# 15-StimChannelSelection.net
KiCad netlist of a schematic drawn in Altium Designer
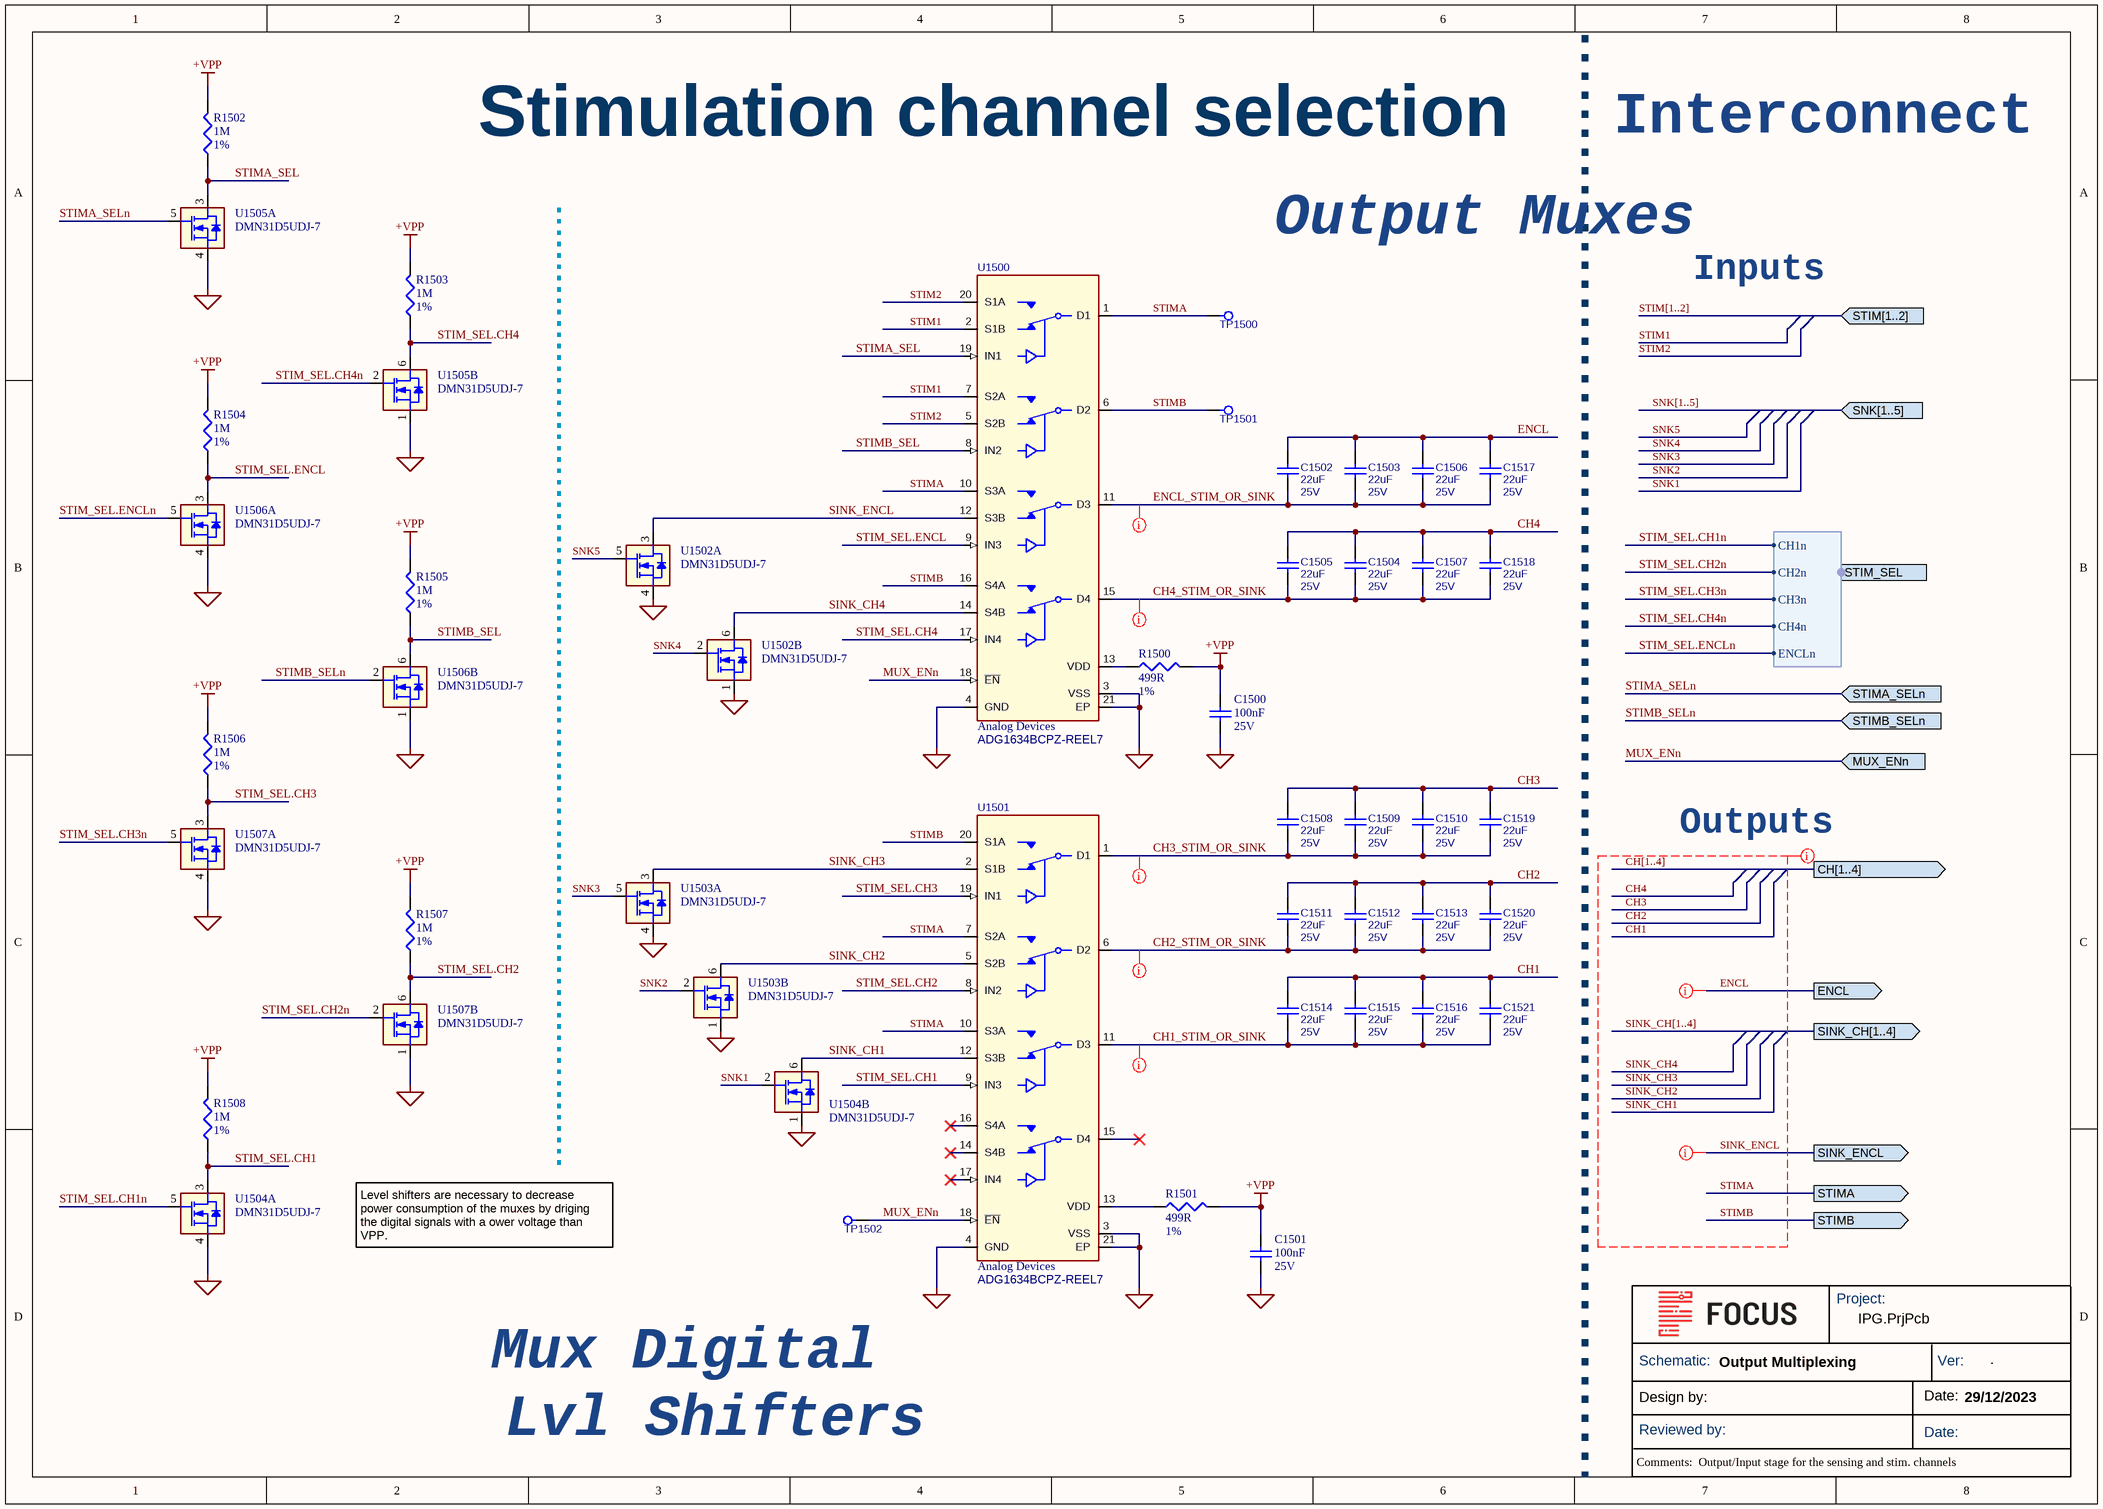
[diagram p0: 15-StimChannelSelection.SchDoc]

(export (version "E")
  (design (tool "Eeschema 10.0.6"))
  (components
    (comp (ref "C1500")
      (value "100nF")
      (footprint "C0201_C")
      (fields
        (field (name "MANUFACTURER") "Murata")
        (field (name "MANUFACTURER PART NUMBER") "GRM033R61E104KE14J")
        (field (name "RATED DC VOLTAGE (URDC)") "25V")
      )
      (libsource (lib "MP-LIBRARY") (part "GRM033R61E104KE14J"))
    )
    (comp (ref "C1501")
      (value "100nF")
      (footprint "C0201_C")
      (fields
        (field (name "MANUFACTURER") "Murata")
        (field (name "MANUFACTURER PART NUMBER") "GRM033R61E104KE14J")
        (field (name "RATED DC VOLTAGE (URDC)") "25V")
      )
      (libsource (lib "MP-LIBRARY") (part "GRM033R61E104KE14J"))
    )
    (comp (ref "C1502")
      (value "22uF")
      (footprint "C0603")
      (description "Capacitor, 22uF, X5S, 25V, 20%, 0603")
      (fields
        (field (name "MANUFACTURER") "Murata")
        (field (name "MANUFACTURER PART NUMBER") "GRM188C61E226ME01J")
        (field (name "RATING") "25V")
      )
      (libsource (lib "MP-LIBRARY") (part "GRM188C61E226ME01J"))
    )
    (comp (ref "C1503")
      (value "22uF")
      (footprint "C0603")
      (description "Capacitor, 22uF, X5S, 25V, 20%, 0603")
      (fields
        (field (name "MANUFACTURER") "Murata")
        (field (name "MANUFACTURER PART NUMBER") "GRM188C61E226ME01J")
        (field (name "RATING") "25V")
      )
      (libsource (lib "MP-LIBRARY") (part "GRM188C61E226ME01J"))
    )
    (comp (ref "C1504")
      (value "22uF")
      (footprint "C0603")
      (description "Capacitor, 22uF, X5S, 25V, 20%, 0603")
      (fields
        (field (name "MANUFACTURER") "Murata")
        (field (name "MANUFACTURER PART NUMBER") "GRM188C61E226ME01J")
        (field (name "RATING") "25V")
      )
      (libsource (lib "MP-LIBRARY") (part "GRM188C61E226ME01J"))
    )
    (comp (ref "C1505")
      (value "22uF")
      (footprint "C0603")
      (description "Capacitor, 22uF, X5S, 25V, 20%, 0603")
      (fields
        (field (name "MANUFACTURER") "Murata")
        (field (name "MANUFACTURER PART NUMBER") "GRM188C61E226ME01J")
        (field (name "RATING") "25V")
      )
      (libsource (lib "MP-LIBRARY") (part "GRM188C61E226ME01J"))
    )
    (comp (ref "C1506")
      (value "22uF")
      (footprint "C0603")
      (description "Capacitor, 22uF, X5S, 25V, 20%, 0603")
      (fields
        (field (name "MANUFACTURER") "Murata")
        (field (name "MANUFACTURER PART NUMBER") "GRM188C61E226ME01J")
        (field (name "RATING") "25V")
      )
      (libsource (lib "MP-LIBRARY") (part "GRM188C61E226ME01J"))
    )
    (comp (ref "C1507")
      (value "22uF")
      (footprint "C0603")
      (description "Capacitor, 22uF, X5S, 25V, 20%, 0603")
      (fields
        (field (name "MANUFACTURER") "Murata")
        (field (name "MANUFACTURER PART NUMBER") "GRM188C61E226ME01J")
        (field (name "RATING") "25V")
      )
      (libsource (lib "MP-LIBRARY") (part "GRM188C61E226ME01J"))
    )
    (comp (ref "C1508")
      (value "22uF")
      (footprint "C0603")
      (description "Capacitor, 22uF, X5S, 25V, 20%, 0603")
      (fields
        (field (name "MANUFACTURER") "Murata")
        (field (name "MANUFACTURER PART NUMBER") "GRM188C61E226ME01J")
        (field (name "RATING") "25V")
      )
      (libsource (lib "MP-LIBRARY") (part "GRM188C61E226ME01J"))
    )
    (comp (ref "C1509")
      (value "22uF")
      (footprint "C0603")
      (description "Capacitor, 22uF, X5S, 25V, 20%, 0603")
      (fields
        (field (name "MANUFACTURER") "Murata")
        (field (name "MANUFACTURER PART NUMBER") "GRM188C61E226ME01J")
        (field (name "RATING") "25V")
      )
      (libsource (lib "MP-LIBRARY") (part "GRM188C61E226ME01J"))
    )
    (comp (ref "C1510")
      (value "22uF")
      (footprint "C0603")
      (description "Capacitor, 22uF, X5S, 25V, 20%, 0603")
      (fields
        (field (name "MANUFACTURER") "Murata")
        (field (name "MANUFACTURER PART NUMBER") "GRM188C61E226ME01J")
        (field (name "RATING") "25V")
      )
      (libsource (lib "MP-LIBRARY") (part "GRM188C61E226ME01J"))
    )
    (comp (ref "C1511")
      (value "22uF")
      (footprint "C0603")
      (description "Capacitor, 22uF, X5S, 25V, 20%, 0603")
      (fields
        (field (name "MANUFACTURER") "Murata")
        (field (name "MANUFACTURER PART NUMBER") "GRM188C61E226ME01J")
        (field (name "RATING") "25V")
      )
      (libsource (lib "MP-LIBRARY") (part "GRM188C61E226ME01J"))
    )
    (comp (ref "C1512")
      (value "22uF")
      (footprint "C0603")
      (description "Capacitor, 22uF, X5S, 25V, 20%, 0603")
      (fields
        (field (name "MANUFACTURER") "Murata")
        (field (name "MANUFACTURER PART NUMBER") "GRM188C61E226ME01J")
        (field (name "RATING") "25V")
      )
      (libsource (lib "MP-LIBRARY") (part "GRM188C61E226ME01J"))
    )
    (comp (ref "C1513")
      (value "22uF")
      (footprint "C0603")
      (description "Capacitor, 22uF, X5S, 25V, 20%, 0603")
      (fields
        (field (name "MANUFACTURER") "Murata")
        (field (name "MANUFACTURER PART NUMBER") "GRM188C61E226ME01J")
        (field (name "RATING") "25V")
      )
      (libsource (lib "MP-LIBRARY") (part "GRM188C61E226ME01J"))
    )
    (comp (ref "C1514")
      (value "22uF")
      (footprint "C0603")
      (description "Capacitor, 22uF, X5S, 25V, 20%, 0603")
      (fields
        (field (name "MANUFACTURER") "Murata")
        (field (name "MANUFACTURER PART NUMBER") "GRM188C61E226ME01J")
        (field (name "RATING") "25V")
      )
      (libsource (lib "MP-LIBRARY") (part "GRM188C61E226ME01J"))
    )
    (comp (ref "C1515")
      (value "22uF")
      (footprint "C0603")
      (description "Capacitor, 22uF, X5S, 25V, 20%, 0603")
      (fields
        (field (name "MANUFACTURER") "Murata")
        (field (name "MANUFACTURER PART NUMBER") "GRM188C61E226ME01J")
        (field (name "RATING") "25V")
      )
      (libsource (lib "MP-LIBRARY") (part "GRM188C61E226ME01J"))
    )
    (comp (ref "C1516")
      (value "22uF")
      (footprint "C0603")
      (description "Capacitor, 22uF, X5S, 25V, 20%, 0603")
      (fields
        (field (name "MANUFACTURER") "Murata")
        (field (name "MANUFACTURER PART NUMBER") "GRM188C61E226ME01J")
        (field (name "RATING") "25V")
      )
      (libsource (lib "MP-LIBRARY") (part "GRM188C61E226ME01J"))
    )
    (comp (ref "C1517")
      (value "22uF")
      (footprint "C0603")
      (description "Capacitor, 22uF, X5S, 25V, 20%, 0603")
      (fields
        (field (name "MANUFACTURER") "Murata")
        (field (name "MANUFACTURER PART NUMBER") "GRM188C61E226ME01J")
        (field (name "RATING") "25V")
      )
      (libsource (lib "MP-LIBRARY") (part "GRM188C61E226ME01J"))
    )
    (comp (ref "C1518")
      (value "22uF")
      (footprint "C0603")
      (description "Capacitor, 22uF, X5S, 25V, 20%, 0603")
      (fields
        (field (name "MANUFACTURER") "Murata")
        (field (name "MANUFACTURER PART NUMBER") "GRM188C61E226ME01J")
        (field (name "RATING") "25V")
      )
      (libsource (lib "MP-LIBRARY") (part "GRM188C61E226ME01J"))
    )
    (comp (ref "C1519")
      (value "22uF")
      (footprint "C0603")
      (description "Capacitor, 22uF, X5S, 25V, 20%, 0603")
      (fields
        (field (name "MANUFACTURER") "Murata")
        (field (name "MANUFACTURER PART NUMBER") "GRM188C61E226ME01J")
        (field (name "RATING") "25V")
      )
      (libsource (lib "MP-LIBRARY") (part "GRM188C61E226ME01J"))
    )
    (comp (ref "C1520")
      (value "22uF")
      (footprint "C0603")
      (description "Capacitor, 22uF, X5S, 25V, 20%, 0603")
      (fields
        (field (name "MANUFACTURER") "Murata")
        (field (name "MANUFACTURER PART NUMBER") "GRM188C61E226ME01J")
        (field (name "RATING") "25V")
      )
      (libsource (lib "MP-LIBRARY") (part "GRM188C61E226ME01J"))
    )
    (comp (ref "C1521")
      (value "22uF")
      (footprint "C0603")
      (description "Capacitor, 22uF, X5S, 25V, 20%, 0603")
      (fields
        (field (name "MANUFACTURER") "Murata")
        (field (name "MANUFACTURER PART NUMBER") "GRM188C61E226ME01J")
        (field (name "RATING") "25V")
      )
      (libsource (lib "MP-LIBRARY") (part "GRM188C61E226ME01J"))
    )
    (comp (ref "R1500")
      (value "499R")
      (footprint "RES0402_REDUCED")
      (fields
        (field (name "MANUFACTURER") "Vishay Dale")
        (field (name "MANUFACTURER PART NUMBER") "CRCW0402499RFKEDHP")
        (field (name "POWER") "200mW")
        (field (name "TOLERANCE") "1%")
      )
      (libsource (lib "MP-LIBRARY") (part "CRCW0402499RFKEDHP"))
    )
    (comp (ref "R1501")
      (value "499R")
      (footprint "RES0402_REDUCED")
      (fields
        (field (name "MANUFACTURER") "Vishay Dale")
        (field (name "MANUFACTURER PART NUMBER") "CRCW0402499RFKEDHP")
        (field (name "POWER") "200mW")
        (field (name "TOLERANCE") "1%")
      )
      (libsource (lib "MP-LIBRARY") (part "CRCW0402499RFKEDHP"))
    )
    (comp (ref "R1502")
      (value "1M")
      (footprint "R0201_C")
      (fields
        (field (name "MANUFACTURER") "Vishay")
        (field (name "MANUFACTURER PART NUMBER") "CRCW02011M00FNED")
        (field (name "TOLERANCE") "1%")
        (field (name "POWER") "50mW")
      )
      (libsource (lib "MP-LIBRARY") (part "CRCW02011M00FNED"))
    )
    (comp (ref "R1503")
      (value "1M")
      (footprint "R0201_C")
      (fields
        (field (name "MANUFACTURER") "Vishay")
        (field (name "MANUFACTURER PART NUMBER") "CRCW02011M00FNED")
        (field (name "TOLERANCE") "1%")
        (field (name "POWER") "50mW")
      )
      (libsource (lib "MP-LIBRARY") (part "CRCW02011M00FNED"))
    )
    (comp (ref "R1504")
      (value "1M")
      (footprint "R0201_C")
      (fields
        (field (name "MANUFACTURER") "Vishay")
        (field (name "MANUFACTURER PART NUMBER") "CRCW02011M00FNED")
        (field (name "TOLERANCE") "1%")
        (field (name "POWER") "50mW")
      )
      (libsource (lib "MP-LIBRARY") (part "CRCW02011M00FNED"))
    )
    (comp (ref "R1505")
      (value "1M")
      (footprint "R0201_C")
      (fields
        (field (name "MANUFACTURER") "Vishay")
        (field (name "MANUFACTURER PART NUMBER") "CRCW02011M00FNED")
        (field (name "TOLERANCE") "1%")
        (field (name "POWER") "50mW")
      )
      (libsource (lib "MP-LIBRARY") (part "CRCW02011M00FNED"))
    )
    (comp (ref "R1506")
      (value "1M")
      (footprint "R0201_C")
      (fields
        (field (name "MANUFACTURER") "Vishay")
        (field (name "MANUFACTURER PART NUMBER") "CRCW02011M00FNED")
        (field (name "TOLERANCE") "1%")
        (field (name "POWER") "50mW")
      )
      (libsource (lib "MP-LIBRARY") (part "CRCW02011M00FNED"))
    )
    (comp (ref "R1507")
      (value "1M")
      (footprint "R0201_C")
      (fields
        (field (name "MANUFACTURER") "Vishay")
        (field (name "MANUFACTURER PART NUMBER") "CRCW02011M00FNED")
        (field (name "TOLERANCE") "1%")
        (field (name "POWER") "50mW")
      )
      (libsource (lib "MP-LIBRARY") (part "CRCW02011M00FNED"))
    )
    (comp (ref "R1508")
      (value "1M")
      (footprint "R0201_C")
      (fields
        (field (name "MANUFACTURER") "Vishay")
        (field (name "MANUFACTURER PART NUMBER") "CRCW02011M00FNED")
        (field (name "TOLERANCE") "1%")
        (field (name "POWER") "50mW")
      )
      (libsource (lib "MP-LIBRARY") (part "CRCW02011M00FNED"))
    )
    (comp (ref "TP1500")
      (value "Test Point")
      (footprint "testpad_0.9mm")
      (description "Test pad, 0.90mm circular pad")
      (libsource (lib "MP-LIBRARY") (part "Test Point"))
    )
    (comp (ref "TP1501")
      (value "Test Point")
      (footprint "testpad_0.9mm")
      (description "Test pad, 0.90mm circular pad")
      (libsource (lib "MP-LIBRARY") (part "Test Point"))
    )
    (comp (ref "TP1502")
      (value "Test Point")
      (footprint "testpad_0.9mm")
      (description "Test pad, 0.90mm circular pad")
      (libsource (lib "MP-LIBRARY") (part "Test Point"))
    )
    (comp (ref "U1500")
      (value "ADG1634BCPZ-REEL7")
      (footprint "AD_CP-20-10")
      (description "IC SWITCH SPDTX4 4.5OHM 20LFCSP")
      (fields (field (name "MANUFACTURER") "Analog Devices"))
      (libsource (lib "MP-LIBRARY") (part "ADG1634BCPZ-REEL7"))
    )
    (comp (ref "U1501")
      (value "ADG1634BCPZ-REEL7")
      (footprint "AD_CP-20-10")
      (description "IC SWITCH SPDTX4 4.5OHM 20LFCSP")
      (fields (field (name "MANUFACTURER") "Analog Devices"))
      (libsource (lib "MP-LIBRARY") (part "ADG1634BCPZ-REEL7"))
    )
    (comp (ref "U1502")
      (value "DMN31D5UDJ-7")
      (footprint "DIODESINC_SOT-963-6")
      (description "MOSFET 2N-CH 30V 0.22A SOT963")
      (fields (field (name "MANUFACTURER") "Diodes inc."))
      (libsource (lib "MP-LIBRARY") (part "DMN31D5UDJ-7"))
    )
    (comp (ref "U1503")
      (value "DMN31D5UDJ-7")
      (footprint "DIODESINC_SOT-963-6")
      (description "MOSFET 2N-CH 30V 0.22A SOT963")
      (fields (field (name "MANUFACTURER") "Diodes inc."))
      (libsource (lib "MP-LIBRARY") (part "DMN31D5UDJ-7"))
    )
    (comp (ref "U1504")
      (value "DMN31D5UDJ-7")
      (footprint "DIODESINC_SOT-963-6")
      (description "MOSFET 2N-CH 30V 0.22A SOT963")
      (fields (field (name "MANUFACTURER") "Diodes inc."))
      (libsource (lib "MP-LIBRARY") (part "DMN31D5UDJ-7"))
    )
    (comp (ref "U1505")
      (value "DMN31D5UDJ-7")
      (footprint "DIODESINC_SOT-963-6")
      (description "MOSFET 2N-CH 30V 0.22A SOT963")
      (fields (field (name "MANUFACTURER") "Diodes inc."))
      (libsource (lib "MP-LIBRARY") (part "DMN31D5UDJ-7"))
    )
    (comp (ref "U1506")
      (value "DMN31D5UDJ-7")
      (footprint "DIODESINC_SOT-963-6")
      (description "MOSFET 2N-CH 30V 0.22A SOT963")
      (fields (field (name "MANUFACTURER") "Diodes inc."))
      (libsource (lib "MP-LIBRARY") (part "DMN31D5UDJ-7"))
    )
    (comp (ref "U1507")
      (value "DMN31D5UDJ-7")
      (footprint "DIODESINC_SOT-963-6")
      (description "MOSFET 2N-CH 30V 0.22A SOT963")
      (fields (field (name "MANUFACTURER") "Diodes inc."))
      (libsource (lib "MP-LIBRARY") (part "DMN31D5UDJ-7"))
    )
  )
  (nets
    (net (code "2") (name "+VPP") (class "Default")
      (node (ref "C1500") (pin "2") (pinfunction "2_2") (pintype "passive"))
      (node (ref "C1501") (pin "2") (pinfunction "2_2") (pintype "passive"))
      (node (ref "R1500") (pin "2") (pinfunction "2_2") (pintype "passive"))
      (node (ref "R1501") (pin "2") (pinfunction "2_2") (pintype "passive"))
      (node (ref "R1502") (pin "1") (pinfunction "1_1") (pintype "passive"))
      (node (ref "R1503") (pin "1") (pinfunction "1_1") (pintype "passive"))
      (node (ref "R1504") (pin "1") (pinfunction "1_1") (pintype "passive"))
      (node (ref "R1505") (pin "1") (pinfunction "1_1") (pintype "passive"))
      (node (ref "R1506") (pin "1") (pinfunction "1_1") (pintype "passive"))
      (node (ref "R1507") (pin "1") (pinfunction "1_1") (pintype "passive"))
      (node (ref "R1508") (pin "1") (pinfunction "1_1") (pintype "passive"))
    )
    (net (code "3") (name "/CH1") (class "Default")
      (node (ref "C1514") (pin "1") (pinfunction "1_1") (pintype "passive"))
      (node (ref "C1515") (pin "1") (pinfunction "1_1") (pintype "passive"))
      (node (ref "C1516") (pin "1") (pinfunction "1_1") (pintype "passive"))
      (node (ref "C1521") (pin "1") (pinfunction "1_1") (pintype "passive"))
    )
    (net (code "4") (name "/CH1_STIM_OR_SINK") (class "Default")
      (node (ref "C1514") (pin "2") (pinfunction "2_2") (pintype "passive"))
      (node (ref "C1515") (pin "2") (pinfunction "2_2") (pintype "passive"))
      (node (ref "C1516") (pin "2") (pinfunction "2_2") (pintype "passive"))
      (node (ref "C1521") (pin "2") (pinfunction "2_2") (pintype "passive"))
      (node (ref "U1501") (pin "11") (pinfunction "D3_11") (pintype "passive"))
    )
    (net (code "5") (name "/CH2") (class "Default")
      (node (ref "C1511") (pin "1") (pinfunction "1_1") (pintype "passive"))
      (node (ref "C1512") (pin "1") (pinfunction "1_1") (pintype "passive"))
      (node (ref "C1513") (pin "1") (pinfunction "1_1") (pintype "passive"))
      (node (ref "C1520") (pin "1") (pinfunction "1_1") (pintype "passive"))
    )
    (net (code "6") (name "/CH2_STIM_OR_SINK") (class "Default")
      (node (ref "C1511") (pin "2") (pinfunction "2_2") (pintype "passive"))
      (node (ref "C1512") (pin "2") (pinfunction "2_2") (pintype "passive"))
      (node (ref "C1513") (pin "2") (pinfunction "2_2") (pintype "passive"))
      (node (ref "C1520") (pin "2") (pinfunction "2_2") (pintype "passive"))
      (node (ref "U1501") (pin "6") (pinfunction "D2_6") (pintype "passive"))
    )
    (net (code "7") (name "/CH3") (class "Default")
      (node (ref "C1508") (pin "1") (pinfunction "1_1") (pintype "passive"))
      (node (ref "C1509") (pin "1") (pinfunction "1_1") (pintype "passive"))
      (node (ref "C1510") (pin "1") (pinfunction "1_1") (pintype "passive"))
      (node (ref "C1519") (pin "1") (pinfunction "1_1") (pintype "passive"))
    )
    (net (code "8") (name "/CH3_STIM_OR_SINK") (class "Default")
      (node (ref "C1508") (pin "2") (pinfunction "2_2") (pintype "passive"))
      (node (ref "C1509") (pin "2") (pinfunction "2_2") (pintype "passive"))
      (node (ref "C1510") (pin "2") (pinfunction "2_2") (pintype "passive"))
      (node (ref "C1519") (pin "2") (pinfunction "2_2") (pintype "passive"))
      (node (ref "U1501") (pin "1") (pinfunction "D1_1") (pintype "passive"))
    )
    (net (code "9") (name "/CH4") (class "Default")
      (node (ref "C1504") (pin "1") (pinfunction "1_1") (pintype "passive"))
      (node (ref "C1505") (pin "1") (pinfunction "1_1") (pintype "passive"))
      (node (ref "C1507") (pin "1") (pinfunction "1_1") (pintype "passive"))
      (node (ref "C1518") (pin "1") (pinfunction "1_1") (pintype "passive"))
    )
    (net (code "10") (name "/CH4_STIM_OR_SINK") (class "Default")
      (node (ref "C1504") (pin "2") (pinfunction "2_2") (pintype "passive"))
      (node (ref "C1505") (pin "2") (pinfunction "2_2") (pintype "passive"))
      (node (ref "C1507") (pin "2") (pinfunction "2_2") (pintype "passive"))
      (node (ref "C1518") (pin "2") (pinfunction "2_2") (pintype "passive"))
      (node (ref "U1500") (pin "15") (pinfunction "D4_15") (pintype "passive"))
    )
    (net (code "12") (name "/ENCL") (class "Default")
      (node (ref "C1502") (pin "2") (pinfunction "2_2") (pintype "passive"))
      (node (ref "C1503") (pin "2") (pinfunction "2_2") (pintype "passive"))
      (node (ref "C1506") (pin "2") (pinfunction "2_2") (pintype "passive"))
      (node (ref "C1517") (pin "1") (pinfunction "1_1") (pintype "passive"))
    )
    (net (code "13") (name "/ENCL_STIM_OR_SINK") (class "Default")
      (node (ref "C1502") (pin "1") (pinfunction "1_1") (pintype "passive"))
      (node (ref "C1503") (pin "1") (pinfunction "1_1") (pintype "passive"))
      (node (ref "C1506") (pin "1") (pinfunction "1_1") (pintype "passive"))
      (node (ref "C1517") (pin "2") (pinfunction "2_2") (pintype "passive"))
      (node (ref "U1500") (pin "11") (pinfunction "D3_11") (pintype "passive"))
    )
    (net (code "14") (name "/MUX_ENn") (class "Default")
      (node (ref "TP1502") (pin "1") (pinfunction "1_1") (pintype "passive"))
      (node (ref "U1500") (pin "18") (pinfunction "~{EN}_18") (pintype "input"))
      (node (ref "U1501") (pin "18") (pinfunction "~{EN}_18") (pintype "input"))
    )
    (net (code "15") (name "/SINK_CH1") (class "Default")
      (node (ref "U1501") (pin "12") (pinfunction "S3B_12") (pintype "passive"))
      (node (ref "U1504") (pin "6") (pinfunction "6_6") (pintype "passive"))
    )
    (net (code "16") (name "/SINK_CH2") (class "Default")
      (node (ref "U1501") (pin "5") (pinfunction "S2B_5") (pintype "passive"))
      (node (ref "U1503") (pin "6") (pinfunction "6_6") (pintype "passive"))
    )
    (net (code "17") (name "/SINK_CH3") (class "Default")
      (node (ref "U1501") (pin "2") (pinfunction "S1B_2") (pintype "passive"))
      (node (ref "U1503") (pin "3") (pinfunction "3_3") (pintype "passive"))
    )
    (net (code "18") (name "/SINK_CH4") (class "Default")
      (node (ref "U1500") (pin "14") (pinfunction "S4B_14") (pintype "passive"))
      (node (ref "U1502") (pin "6") (pinfunction "6_6") (pintype "passive"))
    )
    (net (code "20") (name "/SINK_ENCL") (class "Default")
      (node (ref "U1500") (pin "12") (pinfunction "S3B_12") (pintype "passive"))
      (node (ref "U1502") (pin "3") (pinfunction "3_3") (pintype "passive"))
    )
    (net (code "21") (name "/SNK1") (class "Default")
      (node (ref "U1504") (pin "2") (pinfunction "2_2") (pintype "passive"))
    )
    (net (code "22") (name "/SNK2") (class "Default")
      (node (ref "U1503") (pin "2") (pinfunction "2_2") (pintype "passive"))
    )
    (net (code "23") (name "/SNK3") (class "Default")
      (node (ref "U1503") (pin "5") (pinfunction "5_5") (pintype "passive"))
    )
    (net (code "24") (name "/SNK4") (class "Default")
      (node (ref "U1502") (pin "2") (pinfunction "2_2") (pintype "passive"))
    )
    (net (code "25") (name "/SNK5") (class "Default")
      (node (ref "U1502") (pin "5") (pinfunction "5_5") (pintype "passive"))
    )
    (net (code "27") (name "/STIM1") (class "Default")
      (node (ref "U1500") (pin "2") (pinfunction "S1B_2") (pintype "passive"))
      (node (ref "U1500") (pin "7") (pinfunction "S2A_7") (pintype "passive"))
    )
    (net (code "28") (name "/STIM2") (class "Default")
      (node (ref "U1500") (pin "20") (pinfunction "S1A_20") (pintype "passive"))
      (node (ref "U1500") (pin "5") (pinfunction "S2B_5") (pintype "passive"))
    )
    (net (code "29") (name "/STIMA") (class "Default")
      (node (ref "TP1500") (pin "1") (pinfunction "1_1") (pintype "passive"))
      (node (ref "U1500") (pin "1") (pinfunction "D1_1") (pintype "passive"))
      (node (ref "U1500") (pin "10") (pinfunction "S3A_10") (pintype "passive"))
      (node (ref "U1501") (pin "10") (pinfunction "S3A_10") (pintype "passive"))
      (node (ref "U1501") (pin "7") (pinfunction "S2A_7") (pintype "passive"))
    )
    (net (code "30") (name "/STIMA_SEL") (class "Default")
      (node (ref "R1502") (pin "2") (pinfunction "2_2") (pintype "passive"))
      (node (ref "U1500") (pin "19") (pinfunction "IN1_19") (pintype "input"))
      (node (ref "U1505") (pin "3") (pinfunction "3_3") (pintype "passive"))
    )
    (net (code "31") (name "/STIMA_SELn") (class "Default")
      (node (ref "U1505") (pin "5") (pinfunction "5_5") (pintype "passive"))
    )
    (net (code "32") (name "/STIMB") (class "Default")
      (node (ref "TP1501") (pin "1") (pinfunction "1_1") (pintype "passive"))
      (node (ref "U1500") (pin "16") (pinfunction "S4A_16") (pintype "passive"))
      (node (ref "U1500") (pin "6") (pinfunction "D2_6") (pintype "passive"))
      (node (ref "U1501") (pin "20") (pinfunction "S1A_20") (pintype "passive"))
    )
    (net (code "33") (name "/STIMB_SEL") (class "Default")
      (node (ref "R1505") (pin "2") (pinfunction "2_2") (pintype "passive"))
      (node (ref "U1500") (pin "8") (pinfunction "IN2_8") (pintype "input"))
      (node (ref "U1506") (pin "6") (pinfunction "6_6") (pintype "passive"))
    )
    (net (code "34") (name "/STIMB_SELn") (class "Default")
      (node (ref "U1506") (pin "2") (pinfunction "2_2") (pintype "passive"))
    )
    (net (code "36") (name "/STIM_SEL.CH1") (class "Default")
      (node (ref "R1508") (pin "2") (pinfunction "2_2") (pintype "passive"))
      (node (ref "U1501") (pin "9") (pinfunction "IN3_9") (pintype "input"))
      (node (ref "U1504") (pin "3") (pinfunction "3_3") (pintype "passive"))
    )
    (net (code "37") (name "/STIM_SEL.CH1n") (class "Default")
      (node (ref "U1504") (pin "5") (pinfunction "5_5") (pintype "passive"))
    )
    (net (code "38") (name "/STIM_SEL.CH2") (class "Default")
      (node (ref "R1507") (pin "2") (pinfunction "2_2") (pintype "passive"))
      (node (ref "U1501") (pin "8") (pinfunction "IN2_8") (pintype "input"))
      (node (ref "U1507") (pin "6") (pinfunction "6_6") (pintype "passive"))
    )
    (net (code "39") (name "/STIM_SEL.CH2n") (class "Default")
      (node (ref "U1507") (pin "2") (pinfunction "2_2") (pintype "passive"))
    )
    (net (code "40") (name "/STIM_SEL.CH3") (class "Default")
      (node (ref "R1506") (pin "2") (pinfunction "2_2") (pintype "passive"))
      (node (ref "U1501") (pin "19") (pinfunction "IN1_19") (pintype "input"))
      (node (ref "U1507") (pin "3") (pinfunction "3_3") (pintype "passive"))
    )
    (net (code "41") (name "/STIM_SEL.CH3n") (class "Default")
      (node (ref "U1507") (pin "5") (pinfunction "5_5") (pintype "passive"))
    )
    (net (code "42") (name "/STIM_SEL.CH4") (class "Default")
      (node (ref "R1503") (pin "2") (pinfunction "2_2") (pintype "passive"))
      (node (ref "U1500") (pin "17") (pinfunction "IN4_17") (pintype "input"))
      (node (ref "U1505") (pin "6") (pinfunction "6_6") (pintype "passive"))
    )
    (net (code "43") (name "/STIM_SEL.CH4n") (class "Default")
      (node (ref "U1505") (pin "2") (pinfunction "2_2") (pintype "passive"))
    )
    (net (code "44") (name "/STIM_SEL.ENCL") (class "Default")
      (node (ref "R1504") (pin "2") (pinfunction "2_2") (pintype "passive"))
      (node (ref "U1500") (pin "9") (pinfunction "IN3_9") (pintype "input"))
      (node (ref "U1506") (pin "3") (pinfunction "3_3") (pintype "passive"))
    )
    (net (code "45") (name "/STIM_SEL.ENCLn") (class "Default")
      (node (ref "U1506") (pin "5") (pinfunction "5_5") (pintype "passive"))
    )
    (net (code "47") (name "GND") (class "Default")
      (node (ref "C1500") (pin "1") (pinfunction "1_1") (pintype "passive"))
      (node (ref "C1501") (pin "1") (pinfunction "1_1") (pintype "passive"))
      (node (ref "U1500") (pin "21") (pinfunction "EP_21") (pintype "power_in"))
      (node (ref "U1500") (pin "3") (pinfunction "VSS_3") (pintype "power_in"))
      (node (ref "U1500") (pin "4") (pinfunction "GND_4") (pintype "power_in"))
      (node (ref "U1501") (pin "21") (pinfunction "EP_21") (pintype "power_in"))
      (node (ref "U1501") (pin "3") (pinfunction "VSS_3") (pintype "power_in"))
      (node (ref "U1501") (pin "4") (pinfunction "GND_4") (pintype "power_in"))
      (node (ref "U1502") (pin "1") (pinfunction "1_1") (pintype "passive"))
      (node (ref "U1502") (pin "4") (pinfunction "4_4") (pintype "passive"))
      (node (ref "U1503") (pin "1") (pinfunction "1_1") (pintype "passive"))
      (node (ref "U1503") (pin "4") (pinfunction "4_4") (pintype "passive"))
      (node (ref "U1504") (pin "1") (pinfunction "1_1") (pintype "passive"))
      (node (ref "U1504") (pin "4") (pinfunction "4_4") (pintype "passive"))
      (node (ref "U1505") (pin "1") (pinfunction "1_1") (pintype "passive"))
      (node (ref "U1505") (pin "4") (pinfunction "4_4") (pintype "passive"))
      (node (ref "U1506") (pin "1") (pinfunction "1_1") (pintype "passive"))
      (node (ref "U1506") (pin "4") (pinfunction "4_4") (pintype "passive"))
      (node (ref "U1507") (pin "1") (pinfunction "1_1") (pintype "passive"))
      (node (ref "U1507") (pin "4") (pinfunction "4_4") (pintype "passive"))
    )
    (net (code "48") (name "Net-(U1500-VDD)") (class "Default")
      (node (ref "R1500") (pin "1") (pinfunction "1_1") (pintype "passive"))
      (node (ref "U1500") (pin "13") (pinfunction "VDD_13") (pintype "power_in"))
    )
    (net (code "49") (name "Net-(U1501-VDD)") (class "Default")
      (node (ref "R1501") (pin "1") (pinfunction "1_1") (pintype "passive"))
      (node (ref "U1501") (pin "13") (pinfunction "VDD_13") (pintype "power_in"))
    )
    (net (code "50") (name "unconnected-(U1501-D4-Pad15)") (class "Default")
      (node (ref "U1501") (pin "15") (pinfunction "D4_15") (pintype "passive+no_connect"))
    )
    (net (code "51") (name "unconnected-(U1501-IN4-Pad17)") (class "Default")
      (node (ref "U1501") (pin "17") (pinfunction "IN4_17") (pintype "input+no_connect"))
    )
    (net (code "52") (name "unconnected-(U1501-S4A-Pad16)") (class "Default")
      (node (ref "U1501") (pin "16") (pinfunction "S4A_16") (pintype "passive+no_connect"))
    )
    (net (code "53") (name "unconnected-(U1501-S4B-Pad14)") (class "Default")
      (node (ref "U1501") (pin "14") (pinfunction "S4B_14") (pintype "passive+no_connect"))
    )
  )
)
